# IOTLoRaSmartGreenhouseNode.net
KiCad netlist of a schematic drawn in Altium Designer
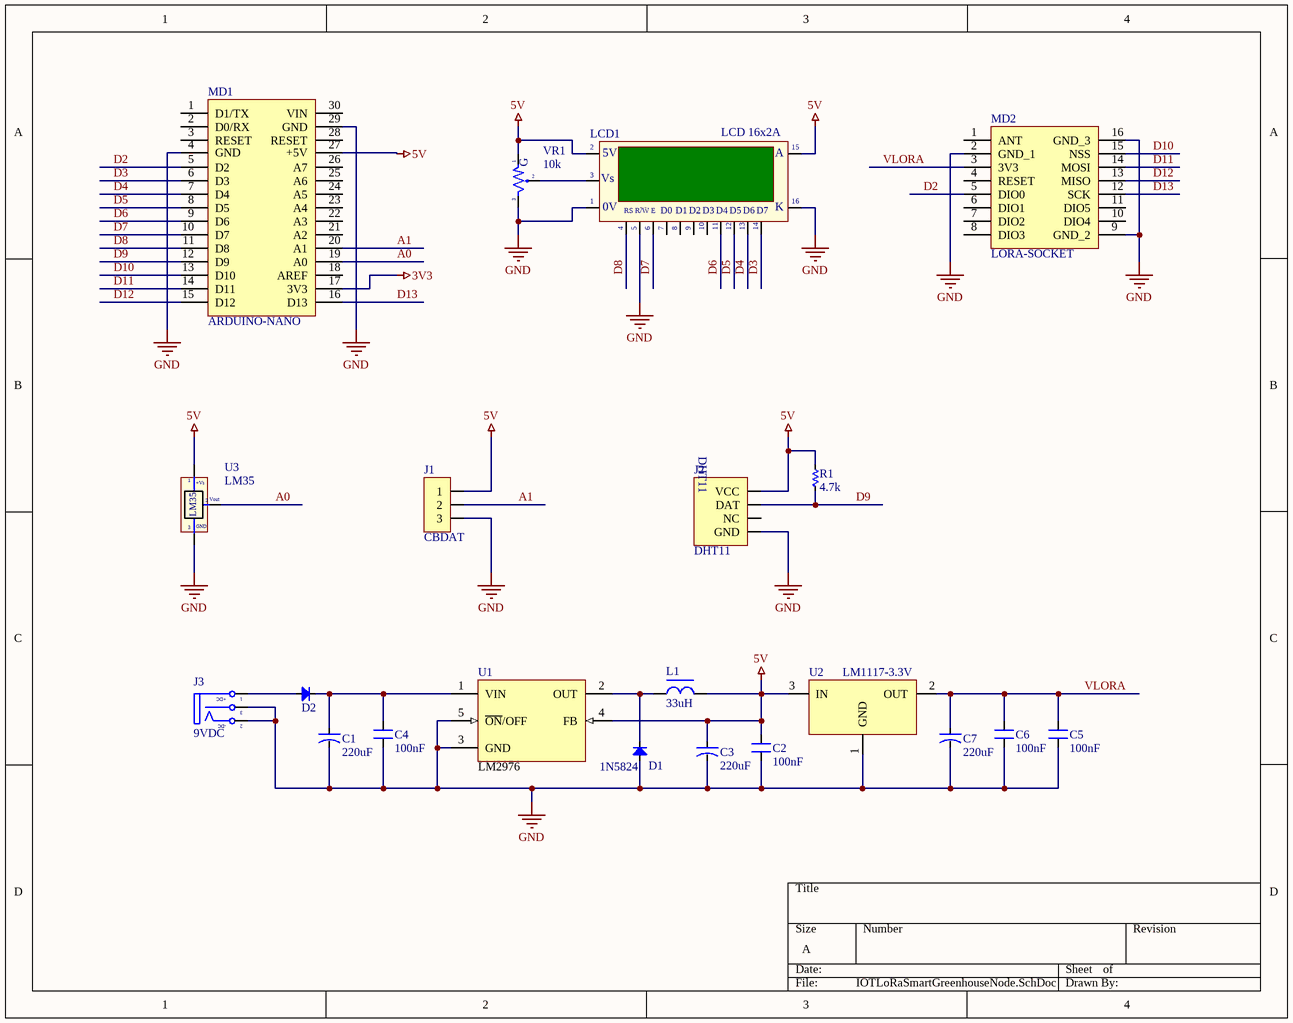
[diagram p0: IOTLoRaSmartGreenhouseNode.SchDoc]

(export (version "E")
  (design (tool "Eeschema 10.0.6"))
  (components
    (comp (ref "C1")
      (value "220uF")
      (footprint "CA-ALU-8")
      (description "Capacitor (Semiconductor SIM Model)")
      (fields (field (name "PUBLISHER") "Altium Limited"))
      (libsource (lib "LIBRARY") (part "CN-ALU-DIP"))
    )
    (comp (ref "C2") (value "100nF") (footprint "CN1.5") (libsource (lib "LIBRARY") (part "CN")))
    (comp (ref "C3")
      (value "220uF")
      (footprint "CA-ALU-8")
      (description "Capacitor (Semiconductor SIM Model)")
      (fields (field (name "PUBLISHER") "Altium Limited"))
      (libsource (lib "LIBRARY") (part "CN-ALU-DIP"))
    )
    (comp (ref "C4") (value "100nF") (footprint "CN1.5") (libsource (lib "LIBRARY") (part "CN")))
    (comp (ref "C5") (value "100nF") (footprint "CN1.5") (libsource (lib "LIBRARY") (part "CN")))
    (comp (ref "C6") (value "100nF") (footprint "CN1.5") (libsource (lib "LIBRARY") (part "CN")))
    (comp (ref "C7")
      (value "220uF")
      (footprint "CA-ALU-8")
      (description "Capacitor (Semiconductor SIM Model)")
      (fields (field (name "PUBLISHER") "Altium Limited"))
      (libsource (lib "LIBRARY") (part "CN-ALU-DIP"))
    )
    (comp (ref "D1")
      (value "1N5824")
      (footprint "DIO-5A")
      (description "Default Diode")
      (fields (field (name "PUBLISHER") "Altium Limited"))
      (libsource (lib "LIBRARY") (part "Diode"))
    )
    (comp (ref "D2")
      (value "Diode")
      (footprint "DIO-3A")
      (description "Default Diode")
      (fields (field (name "PUBLISHER") "Altium Limited"))
      (libsource (lib "LIBRARY") (part "Diode"))
    )
    (comp (ref "J1")
      (value "CBDAT")
      (footprint "JP3-D1C")
      (description "WR-PHD 2.54 mm Angled Socket Header")
      (fields
        (field (name "MANUFACTURER") "Würth Elektronik eiSos GmbH")
        (field (name "PARTNO") "613003143121")
        (field (name "CREATED BY") "Karrer Zheng")
      )
      (libsource (lib "LIBRARY") (part "JP3"))
    )
    (comp (ref "J2")
      (value "DHT11")
      (footprint "JP4-C1T")
      (fields
        (field (name "MANUFACTURER") "Würth Elektronik eiSos GmbH")
        (field (name "PARTNO") "613004143121")
        (field (name "CREATED BY") "Karrer Zheng")
      )
      (libsource (lib "LIBRARY") (part "DHT11"))
    )
    (comp (ref "J3")
      (value "9VDC")
      (footprint "DC0")
      (description "Jac DC input")
      (libsource (lib "LIBRARY") (part "DCIN"))
    )
    (comp (ref "L1")
      (value "33uH")
      (footprint "L-DIP-M-10")
      (description "Inductor")
      (libsource (lib "LIBRARY") (part "L-DIP-1"))
    )
    (comp (ref "LCD1")
      (value "LCD 16x2A")
      (footprint "LCD16X2N")
      (description "LCD dipslay 16 char, 2 line")
      (libsource (lib "LIBRARY") (part "LCD16x2A"))
    )
    (comp (ref "MD1")
      (value "ARDUINO-NANO")
      (footprint "ARDUINO-NANO")
      (description "KIT Arduino Nano")
      (libsource (lib "phatvu1294_Lib") (part "ARDUINO-NANO"))
    )
    (comp (ref "MD2")
      (value "LORA-SOCKET")
      (footprint "LORA-SOCKET")
      (description "Socket LoRa RA01 va RA02")
      (libsource (lib "User") (part "LORA-SOCKET"))
    )
    (comp (ref "R1")
      (value "4.7k")
      (footprint "RES-1/4W")
      (description "Res")
      (fields
        (field (name "MANUFACTURER") "Generic Components")
        (field (name "PUBLISHER") "Altium Hobart Technology Centre")
      )
      (libsource (lib "LIBRARY") (part "Res"))
    )
    (comp (ref "U1") (value "LM2976") (footprint "TO263") (libsource (lib "LIBRARY") (part "LM2596")))
    (comp (ref "U2")
      (value "LM1117-3.3V")
      (footprint "SOT223")
      (description "800mA Low-Dropout Linear Regulator")
      (fields (field (name "CREATOR") "Nguyen Ba Bien"))
      (libsource (lib "LIBRARY") (part "LM1117"))
    )
    (comp (ref "U3")
      (value "LM35")
      (footprint "TO92-123")
      (description "Teminal")
      (libsource (lib "LIBRARY") (part "LM35"))
    )
    (comp (ref "VR1")
      (value "10k")
      (footprint "VR-S2")
      (description "Var Resistor")
      (libsource (lib "LIBRARY") (part "VR-S"))
    )
  )
  (nets
    (net (code "1") (name "/A0") (class "Default")
      (node (ref "MD1") (pin "19") (pinfunction "A0_19") (pintype "passive"))
      (node (ref "U3") (pin "2") (pinfunction "Vout_2") (pintype "passive"))
    )
    (net (code "2") (name "/A1") (class "Default")
      (node (ref "J1") (pin "2") (pinfunction "2_2") (pintype "passive"))
      (node (ref "MD1") (pin "20") (pinfunction "A1_20") (pintype "passive"))
    )
    (net (code "3") (name "/D2") (class "Default")
      (node (ref "MD1") (pin "5") (pinfunction "D2_5") (pintype "passive"))
      (node (ref "MD2") (pin "5") (pinfunction "DIO0_5") (pintype "passive"))
    )
    (net (code "4") (name "/D3") (class "Default")
      (node (ref "LCD1") (pin "14") (pinfunction "D7_14") (pintype "passive"))
      (node (ref "MD1") (pin "6") (pinfunction "D3_6") (pintype "passive"))
    )
    (net (code "5") (name "/D4") (class "Default")
      (node (ref "LCD1") (pin "13") (pinfunction "D6_13") (pintype "passive"))
      (node (ref "MD1") (pin "7") (pinfunction "D4_7") (pintype "passive"))
    )
    (net (code "6") (name "/D5") (class "Default")
      (node (ref "LCD1") (pin "12") (pinfunction "D5_12") (pintype "passive"))
      (node (ref "MD1") (pin "8") (pinfunction "D5_8") (pintype "passive"))
    )
    (net (code "7") (name "/D6") (class "Default")
      (node (ref "LCD1") (pin "11") (pinfunction "D4_11") (pintype "passive"))
      (node (ref "MD1") (pin "9") (pinfunction "D6_9") (pintype "passive"))
    )
    (net (code "8") (name "/D7") (class "Default")
      (node (ref "LCD1") (pin "6") (pinfunction "~{EN}_6") (pintype "passive"))
      (node (ref "MD1") (pin "10") (pinfunction "D7_10") (pintype "passive"))
    )
    (net (code "9") (name "/D8") (class "Default")
      (node (ref "LCD1") (pin "4") (pinfunction "RS_4") (pintype "passive"))
      (node (ref "MD1") (pin "11") (pinfunction "D8_11") (pintype "passive"))
    )
    (net (code "10") (name "/D9") (class "Default")
      (node (ref "J2") (pin "2") (pinfunction "DAT_2") (pintype "passive"))
      (node (ref "MD1") (pin "12") (pinfunction "D9_12") (pintype "passive"))
      (node (ref "R1") (pin "2") (pinfunction "2_2") (pintype "passive"))
    )
    (net (code "11") (name "/D10") (class "Default")
      (node (ref "MD1") (pin "13") (pinfunction "D10_13") (pintype "passive"))
      (node (ref "MD2") (pin "15") (pinfunction "NSS_15") (pintype "passive"))
    )
    (net (code "12") (name "/D11") (class "Default")
      (node (ref "MD1") (pin "14") (pinfunction "D11_14") (pintype "passive"))
      (node (ref "MD2") (pin "14") (pinfunction "MOSI_14") (pintype "passive"))
    )
    (net (code "13") (name "/D12") (class "Default")
      (node (ref "MD1") (pin "15") (pinfunction "D12_15") (pintype "passive"))
      (node (ref "MD2") (pin "13") (pinfunction "MISO_13") (pintype "passive"))
    )
    (net (code "14") (name "/D13") (class "Default")
      (node (ref "MD1") (pin "16") (pinfunction "D13_16") (pintype "passive"))
      (node (ref "MD2") (pin "12") (pinfunction "SCK_12") (pintype "passive"))
    )
    (net (code "15") (name "/VLORA") (class "Default")
      (node (ref "C5") (pin "1") (pinfunction "1_1") (pintype "passive"))
      (node (ref "C6") (pin "1") (pinfunction "1_1") (pintype "passive"))
      (node (ref "C7") (pin "1") (pinfunction "1_1") (pintype "passive"))
      (node (ref "MD2") (pin "3") (pinfunction "3V3_3") (pintype "passive"))
      (node (ref "U2") (pin "2") (pinfunction "OUT_2") (pintype "passive"))
    )
    (net (code "16") (name "3V3") (class "Default")
      (node (ref "MD1") (pin "17") (pinfunction "3V3_17") (pintype "passive"))
    )
    (net (code "17") (name "5V") (class "Default")
      (node (ref "C2") (pin "1") (pinfunction "1_1") (pintype "passive"))
      (node (ref "C3") (pin "1") (pinfunction "1_1") (pintype "passive"))
      (node (ref "J1") (pin "1") (pinfunction "1_1") (pintype "passive"))
      (node (ref "J2") (pin "1") (pinfunction "VCC_1") (pintype "passive"))
      (node (ref "L1") (pin "2") (pinfunction "2_2") (pintype "passive"))
      (node (ref "LCD1") (pin "15") (pinfunction "A_15") (pintype "passive"))
      (node (ref "LCD1") (pin "2") (pinfunction "VDD_2") (pintype "passive"))
      (node (ref "MD1") (pin "27") (pinfunction "+5V_27") (pintype "passive"))
      (node (ref "R1") (pin "1") (pinfunction "1_1") (pintype "passive"))
      (node (ref "U1") (pin "4") (pinfunction "FB_4") (pintype "input"))
      (node (ref "U2") (pin "3") (pinfunction "IN_3") (pintype "passive"))
      (node (ref "U3") (pin "1") (pinfunction "+Vs_1") (pintype "passive"))
      (node (ref "VR1") (pin "1") (pinfunction "1_1") (pintype "passive"))
    )
    (net (code "18") (name "GND") (class "Default")
      (node (ref "C1") (pin "2") (pinfunction "2_2") (pintype "passive"))
      (node (ref "C2") (pin "2") (pinfunction "2_2") (pintype "passive"))
      (node (ref "C3") (pin "2") (pinfunction "2_2") (pintype "passive"))
      (node (ref "C4") (pin "2") (pinfunction "2_2") (pintype "passive"))
      (node (ref "C5") (pin "2") (pinfunction "2_2") (pintype "passive"))
      (node (ref "C6") (pin "2") (pinfunction "2_2") (pintype "passive"))
      (node (ref "C7") (pin "2") (pinfunction "2_2") (pintype "passive"))
      (node (ref "D1") (pin "1") (pinfunction "A_1") (pintype "passive"))
      (node (ref "J1") (pin "3") (pinfunction "3_3") (pintype "passive"))
      (node (ref "J2") (pin "4") (pinfunction "GND_4") (pintype "passive"))
      (node (ref "J3") (pin "2") (pinfunction "TN_2") (pintype "passive"))
      (node (ref "J3") (pin "3") (pinfunction "S_3") (pintype "power_in"))
      (node (ref "LCD1") (pin "1") (pinfunction "GND_1") (pintype "passive"))
      (node (ref "LCD1") (pin "16") (pinfunction "K_16") (pintype "passive"))
      (node (ref "LCD1") (pin "5") (pinfunction "R/~{W}_5") (pintype "passive"))
      (node (ref "MD1") (pin "29") (pinfunction "GND_29") (pintype "passive"))
      (node (ref "MD1") (pin "4") (pinfunction "GND_4") (pintype "passive"))
      (node (ref "MD2") (pin "16") (pinfunction "GND_3_16") (pintype "passive"))
      (node (ref "MD2") (pin "2") (pinfunction "GND_1_2") (pintype "passive"))
      (node (ref "MD2") (pin "9") (pinfunction "GND_2_9") (pintype "passive"))
      (node (ref "U1") (pin "3") (pinfunction "GND_3") (pintype "power_in"))
      (node (ref "U1") (pin "5") (pinfunction "~{ON}/OFF_5") (pintype "input"))
      (node (ref "U2") (pin "1") (pinfunction "GND_1") (pintype "passive"))
      (node (ref "U3") (pin "3") (pinfunction "-_3") (pintype "passive"))
      (node (ref "VR1") (pin "3") (pinfunction "3_3") (pintype "passive"))
    )
    (net (code "19") (name "Net-(D1-K)") (class "Default")
      (node (ref "D1") (pin "2") (pinfunction "K_2") (pintype "passive"))
      (node (ref "L1") (pin "1") (pinfunction "1_1") (pintype "passive"))
      (node (ref "U1") (pin "2") (pinfunction "OUT_2") (pintype "power_in"))
    )
    (net (code "20") (name "Net-(D2-A)") (class "Default")
      (node (ref "D2") (pin "1") (pinfunction "A_1") (pintype "passive"))
      (node (ref "J3") (pin "1") (pinfunction "T_1") (pintype "passive"))
    )
    (net (code "21") (name "Net-(D2-K)") (class "Default")
      (node (ref "C1") (pin "1") (pinfunction "1_1") (pintype "passive"))
      (node (ref "C4") (pin "1") (pinfunction "1_1") (pintype "passive"))
      (node (ref "D2") (pin "2") (pinfunction "K_2") (pintype "passive"))
      (node (ref "U1") (pin "1") (pinfunction "VIN_1") (pintype "power_in"))
    )
    (net (code "22") (name "Net-(LCD1-VEE)") (class "Default")
      (node (ref "LCD1") (pin "3") (pinfunction "VEE_3") (pintype "passive"))
      (node (ref "VR1") (pin "2") (pinfunction "2_2") (pintype "passive"))
    )
    (net (code "23") (name "unconnected-(J2-NC-Pad3)") (class "Default")
      (node (ref "J2") (pin "3") (pinfunction "NC_3") (pintype "passive"))
    )
    (net (code "24") (name "unconnected-(LCD1-D0-Pad7)") (class "Default")
      (node (ref "LCD1") (pin "7") (pinfunction "D0_7") (pintype "passive"))
    )
    (net (code "25") (name "unconnected-(LCD1-D1-Pad8)") (class "Default")
      (node (ref "LCD1") (pin "8") (pinfunction "D1_8") (pintype "passive"))
    )
    (net (code "26") (name "unconnected-(LCD1-D2-Pad9)") (class "Default")
      (node (ref "LCD1") (pin "9") (pinfunction "D2_9") (pintype "passive"))
    )
    (net (code "27") (name "unconnected-(LCD1-D3-Pad10)") (class "Default")
      (node (ref "LCD1") (pin "10") (pinfunction "D3_10") (pintype "passive"))
    )
    (net (code "28") (name "unconnected-(MD1-A2-Pad21)") (class "Default")
      (node (ref "MD1") (pin "21") (pinfunction "A2_21") (pintype "passive"))
    )
    (net (code "29") (name "unconnected-(MD1-A3-Pad22)") (class "Default")
      (node (ref "MD1") (pin "22") (pinfunction "A3_22") (pintype "passive"))
    )
    (net (code "30") (name "unconnected-(MD1-A4-Pad23)") (class "Default")
      (node (ref "MD1") (pin "23") (pinfunction "A4_23") (pintype "passive"))
    )
    (net (code "31") (name "unconnected-(MD1-A5-Pad24)") (class "Default")
      (node (ref "MD1") (pin "24") (pinfunction "A5_24") (pintype "passive"))
    )
    (net (code "32") (name "unconnected-(MD1-A6-Pad25)") (class "Default")
      (node (ref "MD1") (pin "25") (pinfunction "A6_25") (pintype "passive"))
    )
    (net (code "33") (name "unconnected-(MD1-A7-Pad26)") (class "Default")
      (node (ref "MD1") (pin "26") (pinfunction "A7_26") (pintype "passive"))
    )
    (net (code "34") (name "unconnected-(MD1-AREF-Pad18)") (class "Default")
      (node (ref "MD1") (pin "18") (pinfunction "AREF_18") (pintype "passive"))
    )
    (net (code "35") (name "unconnected-(MD1-D0{slash}RX-Pad2)") (class "Default")
      (node (ref "MD1") (pin "2") (pinfunction "D0/RX_2") (pintype "passive"))
    )
    (net (code "36") (name "unconnected-(MD1-D1{slash}TX-Pad1)") (class "Default")
      (node (ref "MD1") (pin "1") (pinfunction "D1/TX_1") (pintype "passive"))
    )
    (net (code "37") (name "unconnected-(MD1-RESET-Pad3)") (class "Default")
      (node (ref "MD1") (pin "3") (pinfunction "RESET_3") (pintype "passive"))
    )
    (net (code "38") (name "unconnected-(MD1-RESET-Pad28)") (class "Default")
      (node (ref "MD1") (pin "28") (pinfunction "RESET_28") (pintype "passive"))
    )
    (net (code "39") (name "unconnected-(MD1-VIN-Pad30)") (class "Default")
      (node (ref "MD1") (pin "30") (pinfunction "VIN_30") (pintype "passive"))
    )
    (net (code "40") (name "unconnected-(MD2-ANT-Pad1)") (class "Default")
      (node (ref "MD2") (pin "1") (pinfunction "ANT_1") (pintype "passive"))
    )
    (net (code "41") (name "unconnected-(MD2-DIO1-Pad6)") (class "Default")
      (node (ref "MD2") (pin "6") (pinfunction "DIO1_6") (pintype "passive"))
    )
    (net (code "42") (name "unconnected-(MD2-DIO2-Pad7)") (class "Default")
      (node (ref "MD2") (pin "7") (pinfunction "DIO2_7") (pintype "passive"))
    )
    (net (code "43") (name "unconnected-(MD2-DIO3-Pad8)") (class "Default")
      (node (ref "MD2") (pin "8") (pinfunction "DIO3_8") (pintype "passive"))
    )
    (net (code "44") (name "unconnected-(MD2-DIO4-Pad10)") (class "Default")
      (node (ref "MD2") (pin "10") (pinfunction "DIO4_10") (pintype "passive"))
    )
    (net (code "45") (name "unconnected-(MD2-DIO5-Pad11)") (class "Default")
      (node (ref "MD2") (pin "11") (pinfunction "DIO5_11") (pintype "passive"))
    )
    (net (code "46") (name "unconnected-(MD2-RESET-Pad4)") (class "Default")
      (node (ref "MD2") (pin "4") (pinfunction "RESET_4") (pintype "passive"))
    )
  )
)
